# SCH_555-Circuit_2025-10-19_1.net
KiCad netlist of a schematic drawn in EasyEDA
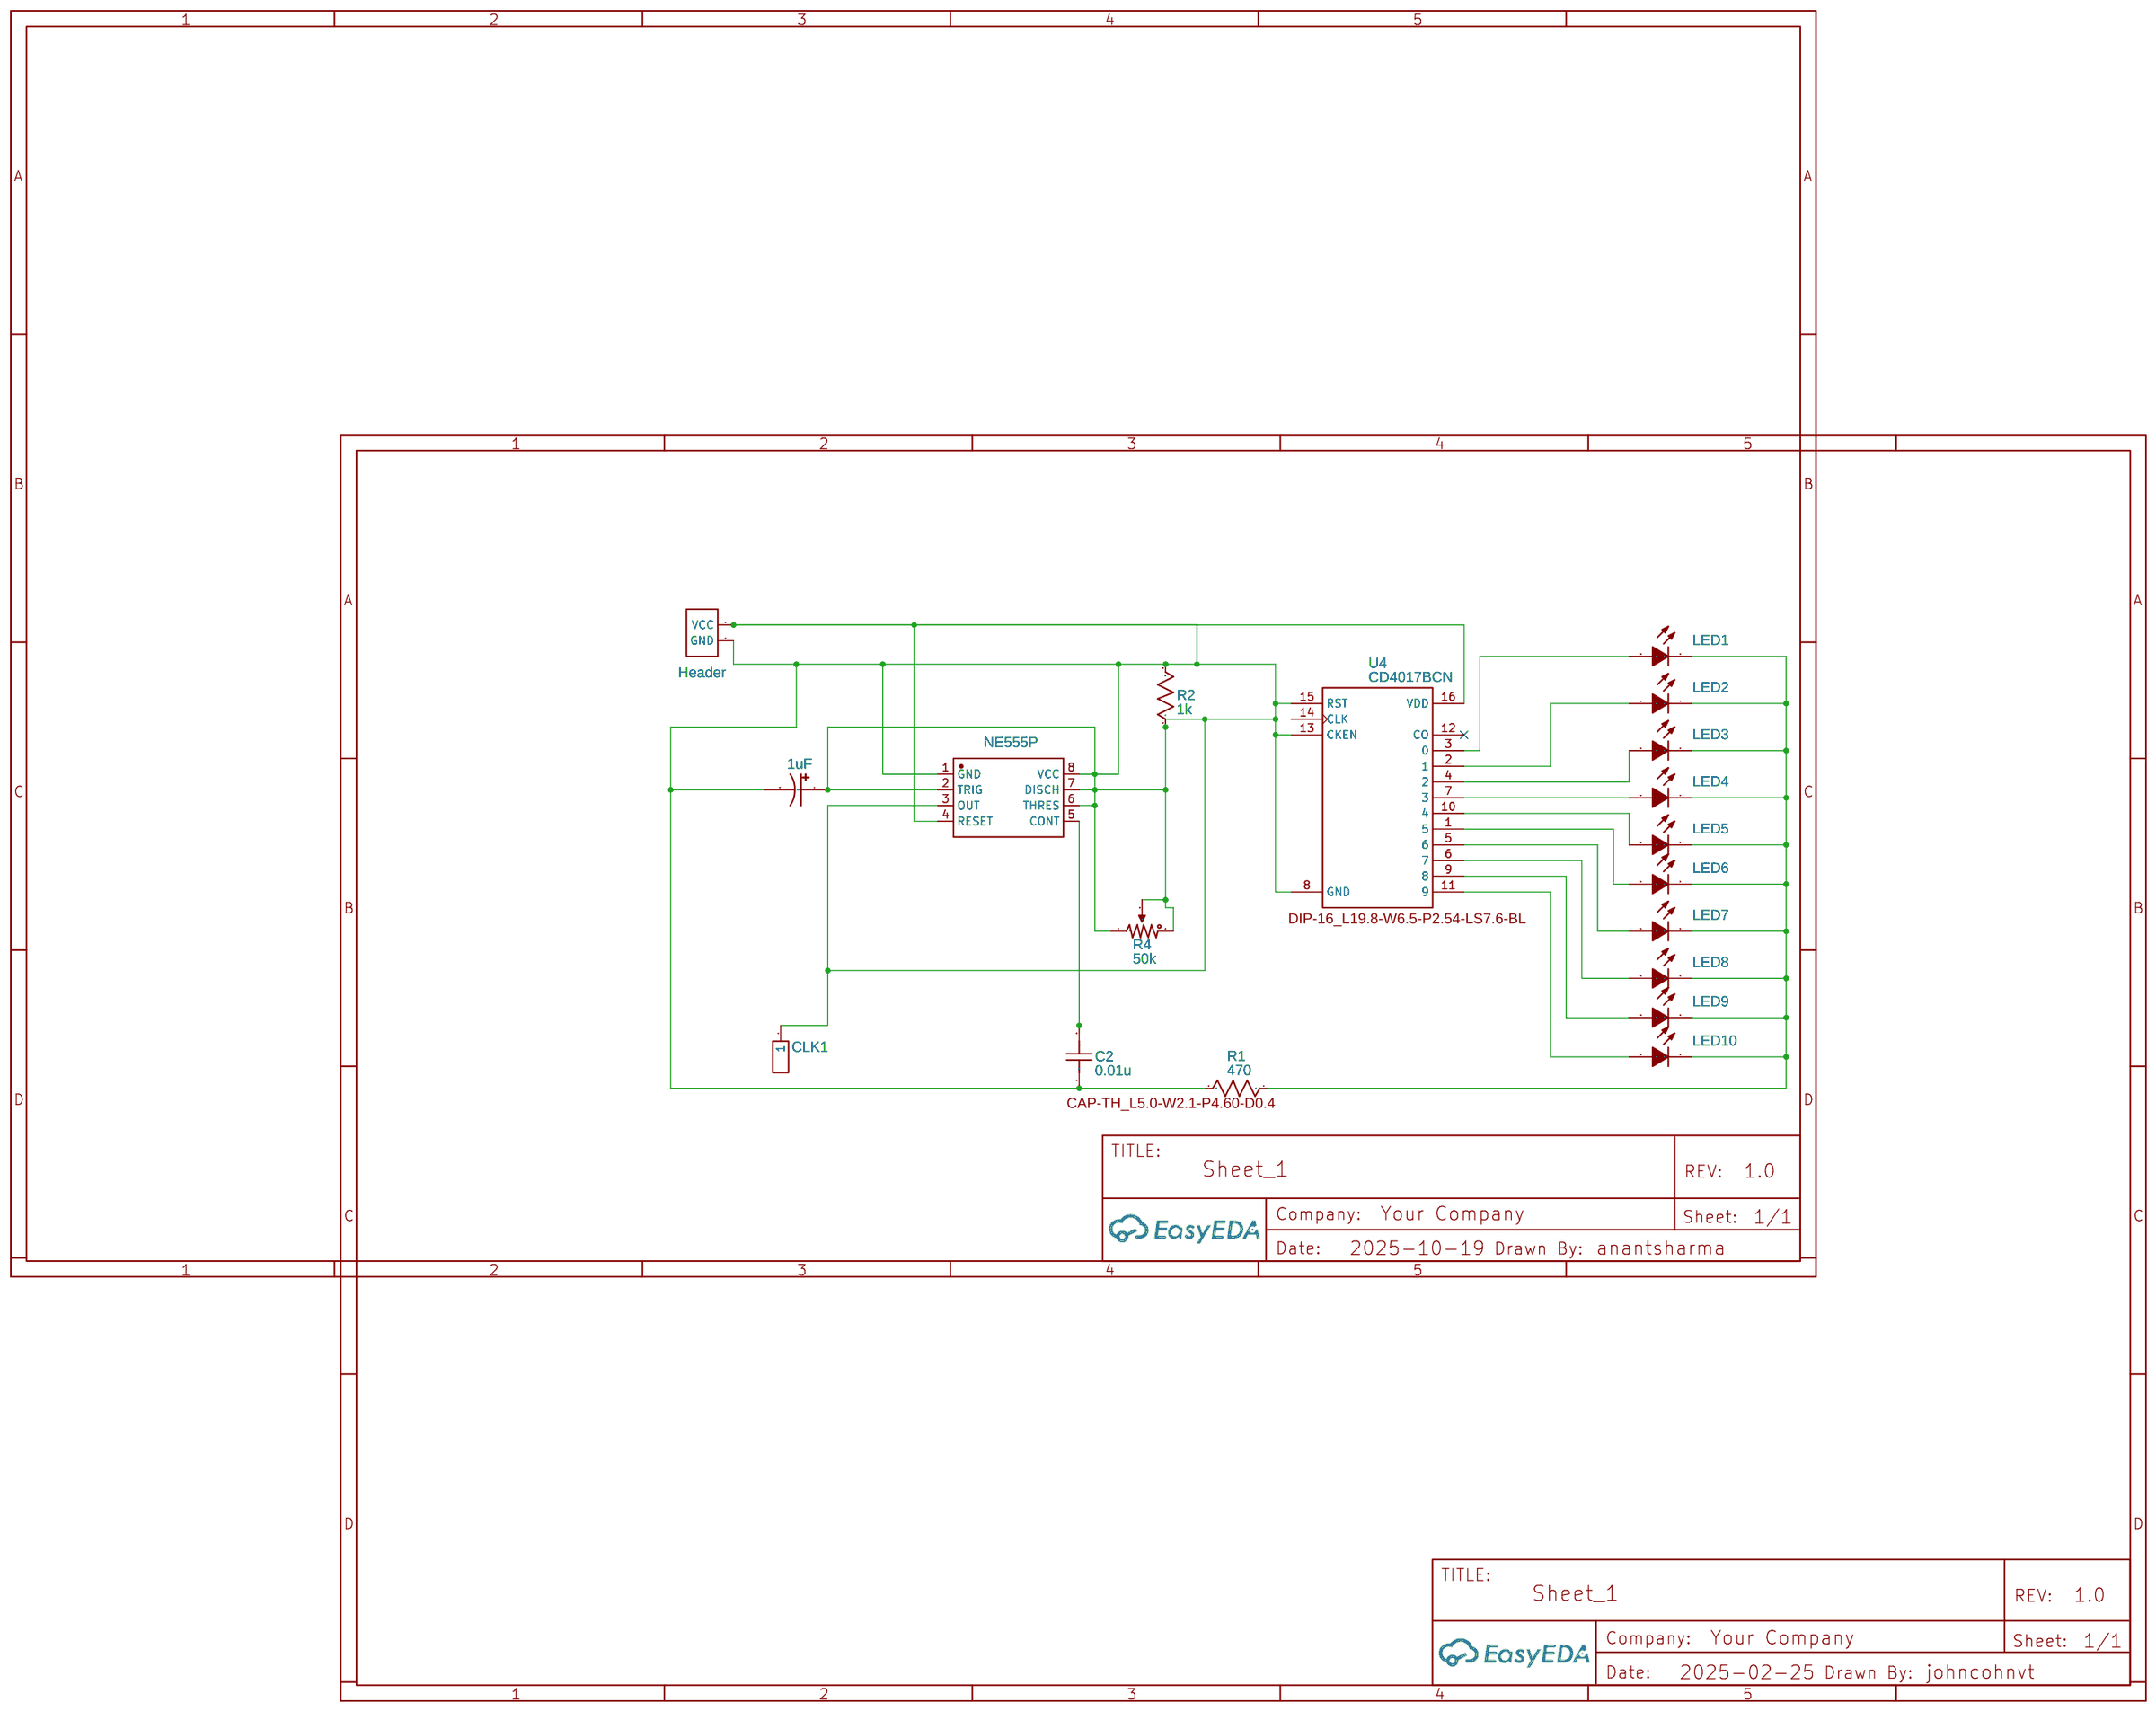
[diagram p0: schematic sheet]

(export (version "E")
  (design (tool "Eeschema 10.0.6"))
  (components
    (comp (ref "C1")
      (value "1uF")
      (fields (field (name "Manufacturer Part") "UVZ1H010MDD") (field (name "Manufacturer") "Nichicon(尼吉康)"))
      (libsource (lib "") (part "UVZ1H010MDD"))
    )
    (comp (ref "C2") (value "0.01u") (libsource (lib "") (part "C_0603_US")))
    (comp (ref "CLK1")
      (value "C81276")
      (fields
        (field (name "Manufacturer Part") "2.54-1*1P针")
        (field (name "Manufacturer") "BOOMELE(Boom Precision Elec)")
      )
      (libsource (lib "") (part "Header-Male-2.54_1x1"))
    )
    (comp (ref "H1") (value "Header") (libsource (lib "") (part "HEADER-FEMALE-2.54_1X2")))
    (comp (ref "LED1") (value "LED_5MM") (libsource (lib "") (part "LED_5MM")))
    (comp (ref "LED2") (value "LED_5MM") (libsource (lib "") (part "LED_5MM")))
    (comp (ref "LED3") (value "LED_5MM") (libsource (lib "") (part "LED_5MM")))
    (comp (ref "LED4") (value "LED_5MM") (libsource (lib "") (part "LED_5MM")))
    (comp (ref "LED5") (value "LED_5MM") (libsource (lib "") (part "LED_5MM")))
    (comp (ref "LED6") (value "LED_5MM") (libsource (lib "") (part "LED_5MM")))
    (comp (ref "LED7") (value "LED_5MM") (libsource (lib "") (part "LED_5MM")))
    (comp (ref "LED8") (value "LED_5MM") (libsource (lib "") (part "LED_5MM")))
    (comp (ref "LED9") (value "LED_5MM") (libsource (lib "") (part "LED_5MM")))
    (comp (ref "LED10") (value "LED_5MM") (libsource (lib "") (part "LED_5MM")))
    (comp (ref "R1")
      (value "470")
      (fields (field (name "Manufacturer Part") "?"))
      (libsource (lib "") (part "Resistor"))
    )
    (comp (ref "R2")
      (value "1k")
      (fields (field (name "Manufacturer Part") "?"))
      (libsource (lib "") (part "Resistor_1"))
    )
    (comp (ref "R4")
      (value "50k")
      (fields (field (name "Manufacturer Part") "?"))
      (libsource (lib "") (part "Potentiometer"))
    )
    (comp (ref "U2")
      (value "NE555P")
      (fields (field (name "Manufacturer") "TI(德州仪器)"))
      (libsource (lib "") (part "NE555P"))
    )
    (comp (ref "U4") (value "CD4017BCN") (libsource (lib "") (part "CD4017BCN")))
  )
  (nets
    (net (code "1") (name "Net-(H1-GND)") (class "Default")
      (node (ref "C1") (pin "1") (pinfunction "1_1") (pintype "unspecified"))
      (node (ref "C1") (pin "2") (pinfunction "2_2") (pintype "unspecified"))
      (node (ref "C2") (pin "1") (pinfunction "1_1") (pintype "unspecified"))
      (node (ref "CLK1") (pin "1") (pinfunction "1_1") (pintype "unspecified"))
      (node (ref "H1") (pin "1") (pinfunction "VCC_1") (pintype "unspecified"))
      (node (ref "H1") (pin "2") (pinfunction "GND_2") (pintype "unspecified"))
      (node (ref "R1") (pin "2") (pinfunction "2_2") (pintype "unspecified"))
      (node (ref "R2") (pin "1") (pinfunction "1_1") (pintype "unspecified"))
      (node (ref "R2") (pin "2") (pinfunction "2_2") (pintype "unspecified"))
      (node (ref "R4") (pin "1") (pinfunction "1_1") (pintype "unspecified"))
      (node (ref "R4") (pin "2") (pinfunction "3_2") (pintype "unspecified"))
      (node (ref "R4") (pin "3") (pinfunction "2_3") (pintype "unspecified"))
      (node (ref "U2") (pin "1") (pinfunction "GND_1") (pintype "unspecified"))
      (node (ref "U2") (pin "2") (pinfunction "TRIG_2") (pintype "unspecified"))
      (node (ref "U2") (pin "3") (pinfunction "OUT_3") (pintype "unspecified"))
      (node (ref "U2") (pin "4") (pinfunction "RESET_4") (pintype "unspecified"))
      (node (ref "U2") (pin "6") (pinfunction "THRES_6") (pintype "unspecified"))
      (node (ref "U2") (pin "7") (pinfunction "DISCH_7") (pintype "unspecified"))
      (node (ref "U2") (pin "8") (pinfunction "VCC_8") (pintype "unspecified"))
      (node (ref "U4") (pin "13") (pinfunction "CKEN_13") (pintype "unspecified"))
      (node (ref "U4") (pin "15") (pinfunction "RST_15") (pintype "unspecified"))
      (node (ref "U4") (pin "16") (pinfunction "VDD_16") (pintype "passive"))
      (node (ref "U4") (pin "8") (pinfunction "GND_8") (pintype "passive"))
    )
    (net (code "2") (name "Net-(LED1-A)") (class "Default")
      (node (ref "LED1") (pin "1") (pinfunction "A_1") (pintype "input"))
      (node (ref "U4") (pin "3") (pinfunction "0_3") (pintype "output"))
    )
    (net (code "3") (name "Net-(LED1-K)") (class "Default")
      (node (ref "LED1") (pin "2") (pinfunction "K_2") (pintype "input"))
      (node (ref "LED10") (pin "2") (pinfunction "K_2") (pintype "input"))
      (node (ref "LED2") (pin "2") (pinfunction "K_2") (pintype "input"))
      (node (ref "LED3") (pin "2") (pinfunction "K_2") (pintype "input"))
      (node (ref "LED4") (pin "2") (pinfunction "K_2") (pintype "input"))
      (node (ref "LED5") (pin "2") (pinfunction "K_2") (pintype "input"))
      (node (ref "LED6") (pin "2") (pinfunction "K_2") (pintype "input"))
      (node (ref "LED7") (pin "2") (pinfunction "K_2") (pintype "input"))
      (node (ref "LED8") (pin "2") (pinfunction "K_2") (pintype "input"))
      (node (ref "LED9") (pin "2") (pinfunction "K_2") (pintype "input"))
      (node (ref "R1") (pin "1") (pinfunction "1_1") (pintype "unspecified"))
    )
    (net (code "4") (name "Net-(LED2-A)") (class "Default")
      (node (ref "LED2") (pin "1") (pinfunction "A_1") (pintype "input"))
      (node (ref "U4") (pin "2") (pinfunction "1_2") (pintype "output"))
    )
    (net (code "5") (name "Net-(LED3-A)") (class "Default")
      (node (ref "LED3") (pin "1") (pinfunction "A_1") (pintype "input"))
      (node (ref "U4") (pin "4") (pinfunction "2_4") (pintype "output"))
    )
    (net (code "6") (name "Net-(LED4-A)") (class "Default")
      (node (ref "LED4") (pin "1") (pinfunction "A_1") (pintype "input"))
      (node (ref "U4") (pin "7") (pinfunction "3_7") (pintype "output"))
    )
    (net (code "7") (name "Net-(LED5-A)") (class "Default")
      (node (ref "LED5") (pin "1") (pinfunction "A_1") (pintype "input"))
      (node (ref "U4") (pin "10") (pinfunction "4_10") (pintype "output"))
    )
    (net (code "8") (name "Net-(LED6-A)") (class "Default")
      (node (ref "LED6") (pin "1") (pinfunction "A_1") (pintype "input"))
      (node (ref "U4") (pin "1") (pinfunction "5_1") (pintype "output"))
    )
    (net (code "9") (name "Net-(LED7-A)") (class "Default")
      (node (ref "LED7") (pin "1") (pinfunction "A_1") (pintype "input"))
      (node (ref "U4") (pin "5") (pinfunction "6_5") (pintype "output"))
    )
    (net (code "10") (name "Net-(LED8-A)") (class "Default")
      (node (ref "LED8") (pin "1") (pinfunction "A_1") (pintype "input"))
      (node (ref "U4") (pin "6") (pinfunction "7_6") (pintype "output"))
    )
    (net (code "11") (name "Net-(LED9-A)") (class "Default")
      (node (ref "LED9") (pin "1") (pinfunction "A_1") (pintype "input"))
      (node (ref "U4") (pin "9") (pinfunction "8_9") (pintype "output"))
    )
    (net (code "12") (name "Net-(LED10-A)") (class "Default")
      (node (ref "LED10") (pin "1") (pinfunction "A_1") (pintype "input"))
      (node (ref "U4") (pin "11") (pinfunction "9_11") (pintype "output"))
    )
    (net (code "13") (name "Net-(U2-CONT)") (class "Default")
      (node (ref "C2") (pin "2") (pinfunction "2_2") (pintype "unspecified"))
      (node (ref "U2") (pin "5") (pinfunction "CONT_5") (pintype "unspecified"))
    )
    (net (code "14") (name "unconnected-(U4-CLK-Pad14)") (class "Default")
      (node (ref "U4") (pin "14") (pinfunction "CLK_14") (pintype "unspecified"))
    )
    (net (code "15") (name "unconnected-(U4-CO-Pad12)") (class "Default")
      (node (ref "U4") (pin "12") (pinfunction "CO_12") (pintype "output+no_connect"))
    )
  )
)
